# pr0board_key.net
KiCad netlist of a schematic drawn in EAGLE
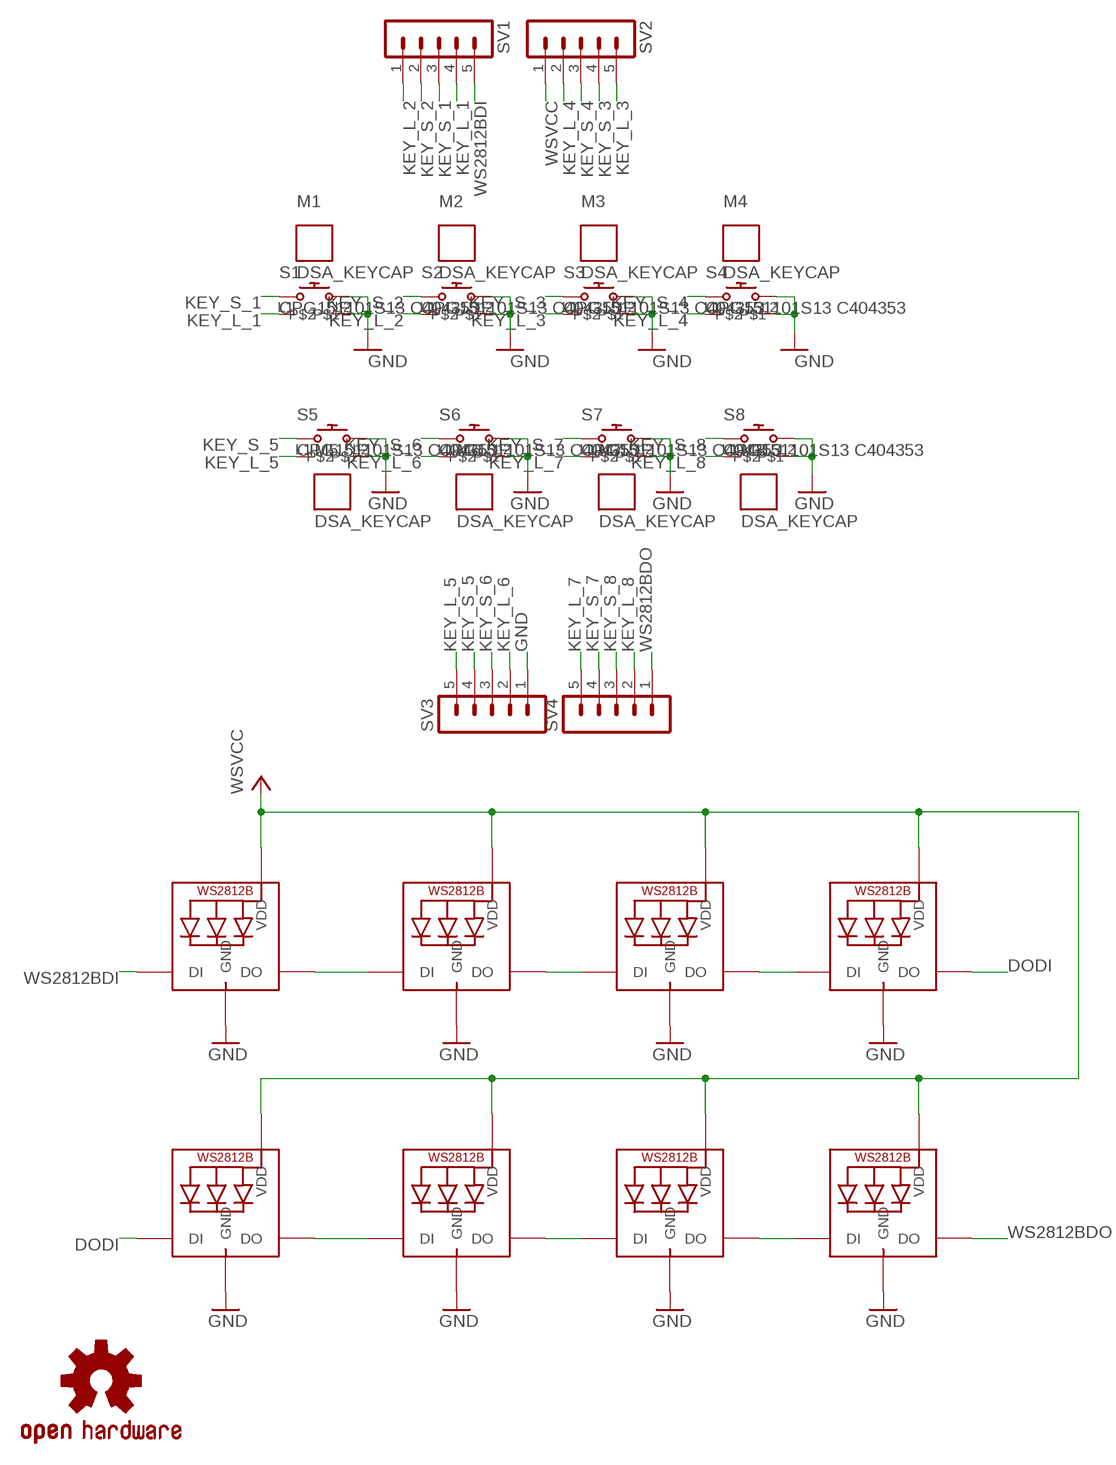
[diagram p0: schematic, sheet 1]

(export (version "E")
  (design (tool "Eeschema 10.0.6"))
  (components
    (comp (ref "LED4")
      (value "WS2812B3535")
      (footprint "eagle-import:LED3535")
      (libsource (lib "eagle-import") (part "WS2812B3535"))
    )
    (comp (ref "LED5")
      (value "WS2812B3535")
      (footprint "eagle-import:LED3535")
      (libsource (lib "eagle-import") (part "WS2812B3535"))
    )
    (comp (ref "LED6")
      (value "WS2812B3535")
      (footprint "eagle-import:LED3535")
      (libsource (lib "eagle-import") (part "WS2812B3535"))
    )
    (comp (ref "LED7")
      (value "WS2812B3535")
      (footprint "eagle-import:LED3535")
      (libsource (lib "eagle-import") (part "WS2812B3535"))
    )
    (comp (ref "LED8")
      (value "WS2812B3535")
      (footprint "eagle-import:LED3535")
      (libsource (lib "eagle-import") (part "WS2812B3535"))
    )
    (comp (ref "LED9")
      (value "WS2812B3535")
      (footprint "eagle-import:LED3535")
      (libsource (lib "eagle-import") (part "WS2812B3535"))
    )
    (comp (ref "LED10")
      (value "WS2812B3535")
      (footprint "eagle-import:LED3535")
      (libsource (lib "eagle-import") (part "WS2812B3535"))
    )
    (comp (ref "LED11")
      (value "WS2812B3535")
      (footprint "eagle-import:LED3535")
      (libsource (lib "eagle-import") (part "WS2812B3535"))
    )
    (comp (ref "M1")
      (value "DSA_KEYCAP")
      (footprint "eagle-import:DSA_KEYCAP")
      (libsource (lib "eagle-import") (part "DSA_KEYCAP"))
    )
    (comp (ref "M2")
      (value "DSA_KEYCAP")
      (footprint "eagle-import:DSA_KEYCAP")
      (libsource (lib "eagle-import") (part "DSA_KEYCAP"))
    )
    (comp (ref "M3")
      (value "DSA_KEYCAP")
      (footprint "eagle-import:DSA_KEYCAP")
      (libsource (lib "eagle-import") (part "DSA_KEYCAP"))
    )
    (comp (ref "M4")
      (value "DSA_KEYCAP")
      (footprint "eagle-import:DSA_KEYCAP")
      (libsource (lib "eagle-import") (part "DSA_KEYCAP"))
    )
    (comp (ref "M5")
      (value "DSA_KEYCAP")
      (footprint "eagle-import:DSA_KEYCAP")
      (libsource (lib "eagle-import") (part "DSA_KEYCAP"))
    )
    (comp (ref "M6")
      (value "DSA_KEYCAP")
      (footprint "eagle-import:DSA_KEYCAP")
      (libsource (lib "eagle-import") (part "DSA_KEYCAP"))
    )
    (comp (ref "M7")
      (value "DSA_KEYCAP")
      (footprint "eagle-import:DSA_KEYCAP")
      (libsource (lib "eagle-import") (part "DSA_KEYCAP"))
    )
    (comp (ref "M8")
      (value "DSA_KEYCAP")
      (footprint "eagle-import:DSA_KEYCAP")
      (libsource (lib "eagle-import") (part "DSA_KEYCAP"))
    )
    (comp (ref "S1")
      (value "CPG151101S13 C404353")
      (footprint "eagle-import:CHERRY_MX_LED")
      (libsource (lib "eagle-import") (part "CHERRY_MX_LED"))
    )
    (comp (ref "S2")
      (value "CPG151101S13 C404353")
      (footprint "eagle-import:CHERRY_MX_LED")
      (libsource (lib "eagle-import") (part "CHERRY_MX_LED"))
    )
    (comp (ref "S3")
      (value "CPG151101S13 C404353")
      (footprint "eagle-import:CHERRY_MX_LED")
      (libsource (lib "eagle-import") (part "CHERRY_MX_LED"))
    )
    (comp (ref "S4")
      (value "CPG151101S13 C404353")
      (footprint "eagle-import:CHERRY_MX_LED")
      (libsource (lib "eagle-import") (part "CHERRY_MX_LED"))
    )
    (comp (ref "S5")
      (value "CPG151101S13 C404353")
      (footprint "eagle-import:CHERRY_MX_LED")
      (libsource (lib "eagle-import") (part "CHERRY_MX_LED"))
    )
    (comp (ref "S6")
      (value "CPG151101S13 C404353")
      (footprint "eagle-import:CHERRY_MX_LED")
      (libsource (lib "eagle-import") (part "CHERRY_MX_LED"))
    )
    (comp (ref "S7")
      (value "CPG151101S13 C404353")
      (footprint "eagle-import:CHERRY_MX_LED")
      (libsource (lib "eagle-import") (part "CHERRY_MX_LED"))
    )
    (comp (ref "S8")
      (value "CPG151101S13 C404353")
      (footprint "eagle-import:CHERRY_MX_LED")
      (libsource (lib "eagle-import") (part "CHERRY_MX_LED"))
    )
    (comp (ref "SV1")
      (value "MA05-1")
      (footprint "eagle-import:MA05-1")
      (libsource (lib "eagle-import") (part "MA05-1"))
    )
    (comp (ref "SV2")
      (value "MA05-1")
      (footprint "eagle-import:MA05-1")
      (libsource (lib "eagle-import") (part "MA05-1"))
    )
    (comp (ref "SV3")
      (value "MA05-1")
      (footprint "eagle-import:MA05-1")
      (libsource (lib "eagle-import") (part "MA05-1"))
    )
    (comp (ref "SV4")
      (value "MA05-1")
      (footprint "eagle-import:MA05-1")
      (libsource (lib "eagle-import") (part "MA05-1"))
    )
    (comp (ref "U$1")
      (value "OSHW-LOGOS")
      (footprint "eagle-import:OSHW-LOGO-S")
      (libsource (lib "eagle-import") (part "OSHW-LOGOS"))
    )
  )
  (nets
    (net (code "1") (name "/DODI") (class "Default")
      (node (ref "LED7") (pin "2") (pinfunction "DO_2") (pintype "output"))
      (node (ref "LED8") (pin "4") (pinfunction "DI_4") (pintype "input"))
    )
    (net (code "2") (name "/KEY_L_1") (class "Default")
      (node (ref "S1") (pin "L1") (pinfunction "P$1_L1") (pintype "bidirectional"))
      (node (ref "SV1") (pin "4") (pinfunction "4_4") (pintype "passive"))
    )
    (net (code "3") (name "/KEY_L_2") (class "Default")
      (node (ref "S2") (pin "L1") (pinfunction "P$1_L1") (pintype "bidirectional"))
      (node (ref "SV1") (pin "1") (pinfunction "1_1") (pintype "passive"))
    )
    (net (code "4") (name "/KEY_L_3") (class "Default")
      (node (ref "S3") (pin "L1") (pinfunction "P$1_L1") (pintype "bidirectional"))
      (node (ref "SV2") (pin "5") (pinfunction "5_5") (pintype "passive"))
    )
    (net (code "5") (name "/KEY_L_4") (class "Default")
      (node (ref "S4") (pin "L1") (pinfunction "P$1_L1") (pintype "bidirectional"))
      (node (ref "SV2") (pin "2") (pinfunction "2_2") (pintype "passive"))
    )
    (net (code "6") (name "/KEY_L_5") (class "Default")
      (node (ref "S5") (pin "L1") (pinfunction "P$1_L1") (pintype "bidirectional"))
      (node (ref "SV3") (pin "5") (pinfunction "5_5") (pintype "passive"))
    )
    (net (code "7") (name "/KEY_L_6") (class "Default")
      (node (ref "S6") (pin "L1") (pinfunction "P$1_L1") (pintype "bidirectional"))
      (node (ref "SV3") (pin "2") (pinfunction "2_2") (pintype "passive"))
    )
    (net (code "8") (name "/KEY_L_7") (class "Default")
      (node (ref "S7") (pin "L1") (pinfunction "P$1_L1") (pintype "bidirectional"))
      (node (ref "SV4") (pin "5") (pinfunction "5_5") (pintype "passive"))
    )
    (net (code "9") (name "/KEY_L_8") (class "Default")
      (node (ref "S8") (pin "L1") (pinfunction "P$1_L1") (pintype "bidirectional"))
      (node (ref "SV4") (pin "2") (pinfunction "2_2") (pintype "passive"))
    )
    (net (code "10") (name "/KEY_S_1") (class "Default")
      (node (ref "S1") (pin "S1") (pinfunction "1_S1") (pintype "passive"))
      (node (ref "SV1") (pin "3") (pinfunction "3_3") (pintype "passive"))
    )
    (net (code "11") (name "/KEY_S_2") (class "Default")
      (node (ref "S2") (pin "S1") (pinfunction "1_S1") (pintype "passive"))
      (node (ref "SV1") (pin "2") (pinfunction "2_2") (pintype "passive"))
    )
    (net (code "12") (name "/KEY_S_3") (class "Default")
      (node (ref "S3") (pin "S1") (pinfunction "1_S1") (pintype "passive"))
      (node (ref "SV2") (pin "4") (pinfunction "4_4") (pintype "passive"))
    )
    (net (code "13") (name "/KEY_S_4") (class "Default")
      (node (ref "S4") (pin "S1") (pinfunction "1_S1") (pintype "passive"))
      (node (ref "SV2") (pin "3") (pinfunction "3_3") (pintype "passive"))
    )
    (net (code "14") (name "/KEY_S_5") (class "Default")
      (node (ref "S5") (pin "S1") (pinfunction "1_S1") (pintype "passive"))
      (node (ref "SV3") (pin "4") (pinfunction "4_4") (pintype "passive"))
    )
    (net (code "15") (name "/KEY_S_6") (class "Default")
      (node (ref "S6") (pin "S1") (pinfunction "1_S1") (pintype "passive"))
      (node (ref "SV3") (pin "3") (pinfunction "3_3") (pintype "passive"))
    )
    (net (code "16") (name "/KEY_S_7") (class "Default")
      (node (ref "S7") (pin "S1") (pinfunction "1_S1") (pintype "passive"))
      (node (ref "SV4") (pin "4") (pinfunction "4_4") (pintype "passive"))
    )
    (net (code "17") (name "/KEY_S_8") (class "Default")
      (node (ref "S8") (pin "S1") (pinfunction "1_S1") (pintype "passive"))
      (node (ref "SV4") (pin "3") (pinfunction "3_3") (pintype "passive"))
    )
    (net (code "18") (name "/WS2812BDI") (class "Default")
      (node (ref "LED4") (pin "4") (pinfunction "DI_4") (pintype "input"))
      (node (ref "SV1") (pin "5") (pinfunction "5_5") (pintype "passive"))
    )
    (net (code "19") (name "/WS2812BDO") (class "Default")
      (node (ref "LED11") (pin "2") (pinfunction "DO_2") (pintype "output"))
      (node (ref "SV4") (pin "1") (pinfunction "1_1") (pintype "passive"))
    )
    (net (code "20") (name "GND") (class "Default")
      (node (ref "LED10") (pin "3") (pinfunction "GND_3") (pintype "power_in"))
      (node (ref "LED11") (pin "3") (pinfunction "GND_3") (pintype "power_in"))
      (node (ref "LED4") (pin "3") (pinfunction "GND_3") (pintype "power_in"))
      (node (ref "LED5") (pin "3") (pinfunction "GND_3") (pintype "power_in"))
      (node (ref "LED6") (pin "3") (pinfunction "GND_3") (pintype "power_in"))
      (node (ref "LED7") (pin "3") (pinfunction "GND_3") (pintype "power_in"))
      (node (ref "LED8") (pin "3") (pinfunction "GND_3") (pintype "power_in"))
      (node (ref "LED9") (pin "3") (pinfunction "GND_3") (pintype "power_in"))
      (node (ref "S1") (pin "L2") (pinfunction "P$2_L2") (pintype "bidirectional"))
      (node (ref "S1") (pin "S2") (pinfunction "2_S2") (pintype "passive"))
      (node (ref "S2") (pin "L2") (pinfunction "P$2_L2") (pintype "bidirectional"))
      (node (ref "S2") (pin "S2") (pinfunction "2_S2") (pintype "passive"))
      (node (ref "S3") (pin "L2") (pinfunction "P$2_L2") (pintype "bidirectional"))
      (node (ref "S3") (pin "S2") (pinfunction "2_S2") (pintype "passive"))
      (node (ref "S4") (pin "L2") (pinfunction "P$2_L2") (pintype "bidirectional"))
      (node (ref "S4") (pin "S2") (pinfunction "2_S2") (pintype "passive"))
      (node (ref "S5") (pin "L2") (pinfunction "P$2_L2") (pintype "bidirectional"))
      (node (ref "S5") (pin "S2") (pinfunction "2_S2") (pintype "passive"))
      (node (ref "S6") (pin "L2") (pinfunction "P$2_L2") (pintype "bidirectional"))
      (node (ref "S6") (pin "S2") (pinfunction "2_S2") (pintype "passive"))
      (node (ref "S7") (pin "L2") (pinfunction "P$2_L2") (pintype "bidirectional"))
      (node (ref "S7") (pin "S2") (pinfunction "2_S2") (pintype "passive"))
      (node (ref "S8") (pin "L2") (pinfunction "P$2_L2") (pintype "bidirectional"))
      (node (ref "S8") (pin "S2") (pinfunction "2_S2") (pintype "passive"))
      (node (ref "SV3") (pin "1") (pinfunction "1_1") (pintype "passive"))
    )
    (net (code "21") (name "Net-(LED4-DO)") (class "Default")
      (node (ref "LED4") (pin "2") (pinfunction "DO_2") (pintype "output"))
      (node (ref "LED5") (pin "4") (pinfunction "DI_4") (pintype "input"))
    )
    (net (code "22") (name "Net-(LED5-DO)") (class "Default")
      (node (ref "LED5") (pin "2") (pinfunction "DO_2") (pintype "output"))
      (node (ref "LED6") (pin "4") (pinfunction "DI_4") (pintype "input"))
    )
    (net (code "23") (name "Net-(LED6-DO)") (class "Default")
      (node (ref "LED6") (pin "2") (pinfunction "DO_2") (pintype "output"))
      (node (ref "LED7") (pin "4") (pinfunction "DI_4") (pintype "input"))
    )
    (net (code "24") (name "Net-(LED8-DO)") (class "Default")
      (node (ref "LED8") (pin "2") (pinfunction "DO_2") (pintype "output"))
      (node (ref "LED9") (pin "4") (pinfunction "DI_4") (pintype "input"))
    )
    (net (code "25") (name "Net-(LED10-DI)") (class "Default")
      (node (ref "LED10") (pin "4") (pinfunction "DI_4") (pintype "input"))
      (node (ref "LED9") (pin "2") (pinfunction "DO_2") (pintype "output"))
    )
    (net (code "26") (name "Net-(LED10-DO)") (class "Default")
      (node (ref "LED10") (pin "2") (pinfunction "DO_2") (pintype "output"))
      (node (ref "LED11") (pin "4") (pinfunction "DI_4") (pintype "input"))
    )
    (net (code "27") (name "WSVCC") (class "Default")
      (node (ref "LED10") (pin "1") (pinfunction "VDD_1") (pintype "power_in"))
      (node (ref "LED11") (pin "1") (pinfunction "VDD_1") (pintype "power_in"))
      (node (ref "LED4") (pin "1") (pinfunction "VDD_1") (pintype "power_in"))
      (node (ref "LED5") (pin "1") (pinfunction "VDD_1") (pintype "power_in"))
      (node (ref "LED6") (pin "1") (pinfunction "VDD_1") (pintype "power_in"))
      (node (ref "LED7") (pin "1") (pinfunction "VDD_1") (pintype "power_in"))
      (node (ref "LED8") (pin "1") (pinfunction "VDD_1") (pintype "power_in"))
      (node (ref "LED9") (pin "1") (pinfunction "VDD_1") (pintype "power_in"))
      (node (ref "SV2") (pin "1") (pinfunction "1_1") (pintype "passive"))
    )
  )
)
